# MCU_IMU.net
KiCad netlist of a schematic drawn in Altium Designer
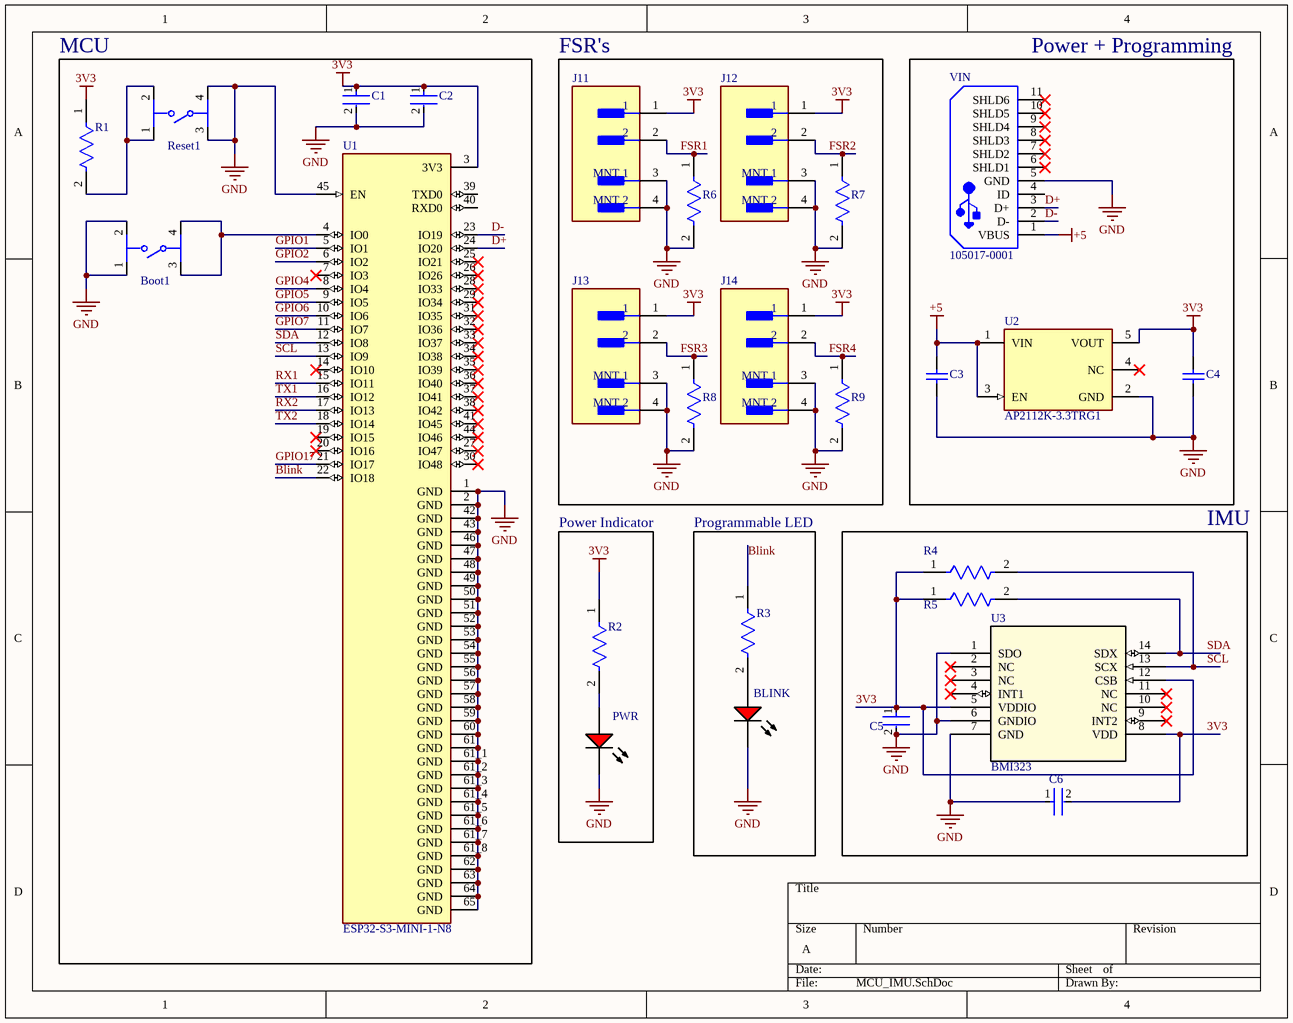
[diagram p0: MCU_IMU.SchDoc]

(export (version "E")
  (design (tool "Eeschema 10.0.6"))
  (components
    (comp (ref "BLINK")
      (value "SML-LX1206IC-TR")
      (footprint "LUMX-SML-LX1206IC_V")
      (description "LED Red, 65 mW, -40 to 85 degC, 2-Pin SMD, RoHS, Tape and Reel")
      (fields (field (name "MANUFACTURER") "Lumex"))
      (libsource (lib "Altium Content Vault") (part "LED-RED-AK-2"))
    )
    (comp (ref "Boot1")
      (value "PTS810SJM250SMTRLFS")
      (footprint "FP-PTS810SJM250SMTRLFS-MFG")
      (description "SWITCH TACTILE SPST-NO 0.05A 16V")
      (libsource (lib "Altium Content Vault") (part "1adf0dd01260c80cf25a44bfd6b99ba"))
    )
    (comp (ref "C1")
      (value "CC0805KRX7R9BB104")
      (footprint "FP-CC0805-0_85-MFG")
      (description "CAP CER 0.1UF 50V X7R 0805")
      (fields (field (name "TOLERANCE") "0.1") (field (name "MANUFACTURER") "Yageo"))
      (libsource (lib "Altium Content Vault") (part "11868f565c42a9108669ba33697ecf6"))
    )
    (comp (ref "C2")
      (value "CC0805KRX7R9BB104")
      (footprint "FP-CC0805-0_85-MFG")
      (description "CAP CER 0.1UF 50V X7R 0805")
      (fields (field (name "TOLERANCE") "0.1") (field (name "MANUFACTURER") "Yageo"))
      (libsource (lib "Altium Content Vault") (part "11868f565c42a9108669ba33697ecf6"))
    )
    (comp (ref "C3")
      (value "C0805C105K5RACTU")
      (footprint "CAPC2013X140X50ML20T25")
      (fields (field (name "MANUFACTURER") "Kemet"))
      (libsource (lib "Altium Content Vault") (part "CAP"))
    )
    (comp (ref "C4")
      (value "C0805C105K5RACTU")
      (footprint "CAPC2013X140X50ML20T25")
      (fields (field (name "MANUFACTURER") "Kemet"))
      (libsource (lib "Altium Content Vault") (part "CAP"))
    )
    (comp (ref "C5")
      (value "CC0805KRX7R9BB104")
      (footprint "FP-CC0805-0_85-MFG")
      (description "CAP CER 0.1UF 50V X7R 0805")
      (fields (field (name "TOLERANCE") "0.1") (field (name "MANUFACTURER") "Yageo"))
      (libsource (lib "Altium Content Vault") (part "11868f565c42a9108669ba33697ecf6"))
    )
    (comp (ref "C6")
      (value "CC0805KRX7R9BB104")
      (footprint "FP-CC0805-0_85-MFG")
      (description "CAP CER 0.1UF 50V X7R 0805")
      (fields (field (name "TOLERANCE") "0.1") (field (name "MANUFACTURER") "Yageo"))
      (libsource (lib "Altium Content Vault") (part "11868f565c42a9108669ba33697ecf6"))
    )
    (comp (ref "J11")
      (value "BM02B-SRSS-TBT(LF)(SN)")
      (footprint "FP-BM02B-SRSS-TBT_LF_SN-MFG")
      (description "CONN WIRE HDR 2POS 1MM STSMD")
      (libsource (lib "Altium Content Vault") (part "029478cb6d4f2fad0cd2a245525ee6d"))
    )
    (comp (ref "J12")
      (value "BM02B-SRSS-TBT(LF)(SN)")
      (footprint "FP-BM02B-SRSS-TBT_LF_SN-MFG")
      (description "CONN WIRE HDR 2POS 1MM STSMD")
      (libsource (lib "Altium Content Vault") (part "029478cb6d4f2fad0cd2a245525ee6d"))
    )
    (comp (ref "J13")
      (value "BM02B-SRSS-TBT(LF)(SN)")
      (footprint "FP-BM02B-SRSS-TBT_LF_SN-MFG")
      (description "CONN WIRE HDR 2POS 1MM STSMD")
      (libsource (lib "Altium Content Vault") (part "029478cb6d4f2fad0cd2a245525ee6d"))
    )
    (comp (ref "J14")
      (value "BM02B-SRSS-TBT(LF)(SN)")
      (footprint "FP-BM02B-SRSS-TBT_LF_SN-MFG")
      (description "CONN WIRE HDR 2POS 1MM STSMD")
      (libsource (lib "Altium Content Vault") (part "029478cb6d4f2fad0cd2a245525ee6d"))
    )
    (comp (ref "PWR")
      (value "SML-LX1206IC-TR")
      (footprint "LUMX-SML-LX1206IC_V")
      (description "LED Red, 65 mW, -40 to 85 degC, 2-Pin SMD, RoHS, Tape and Reel")
      (fields (field (name "MANUFACTURER") "Lumex"))
      (libsource (lib "Altium Content Vault") (part "LED-RED-AK-2"))
    )
    (comp (ref "R1")
      (value "CRCW08054K70FKEA")
      (footprint "FP-CRCW0805-e3-IPC_B")
      (description "RES Thick Film, 4.7kΩ, 1%, 0.125W, 100ppm/°C, 0805")
      (fields (field (name "TOLERANCE") "1%"))
      (libsource (lib "Altium Content Vault") (part "1029c3af85768c4190bb7ad29bc67b5"))
    )
    (comp (ref "R2")
      (value "CRCW08054K70FKEA")
      (footprint "FP-CRCW0805-e3-IPC_B")
      (description "RES Thick Film, 4.7kΩ, 1%, 0.125W, 100ppm/°C, 0805")
      (fields (field (name "TOLERANCE") "1%"))
      (libsource (lib "Altium Content Vault") (part "1029c3af85768c4190bb7ad29bc67b5"))
    )
    (comp (ref "R3")
      (value "CRCW08054K70FKEA")
      (footprint "FP-CRCW0805-e3-IPC_B")
      (description "RES Thick Film, 4.7kΩ, 1%, 0.125W, 100ppm/°C, 0805")
      (fields (field (name "TOLERANCE") "1%"))
      (libsource (lib "Altium Content Vault") (part "1029c3af85768c4190bb7ad29bc67b5"))
    )
    (comp (ref "R4")
      (value "CRCW08054K70FKEA")
      (footprint "FP-CRCW0805-e3-IPC_B")
      (description "RES Thick Film, 4.7kΩ, 1%, 0.125W, 100ppm/°C, 0805")
      (fields (field (name "TOLERANCE") "1%"))
      (libsource (lib "Altium Content Vault") (part "1029c3af85768c4190bb7ad29bc67b5"))
    )
    (comp (ref "R5")
      (value "CRCW08054K70FKEA")
      (footprint "FP-CRCW0805-e3-IPC_B")
      (description "RES Thick Film, 4.7kΩ, 1%, 0.125W, 100ppm/°C, 0805")
      (fields (field (name "TOLERANCE") "1%"))
      (libsource (lib "Altium Content Vault") (part "1029c3af85768c4190bb7ad29bc67b5"))
    )
    (comp (ref "R6")
      (value "RC0603FR-0710KL")
      (footprint "FP-RC0603-0_55-IPC_C")
      (description "RES 10K OHM 1% 1/10W 0603")
      (fields (field (name "TOLERANCE") "1%"))
      (libsource (lib "Altium Content Vault") (part "1029c3af85768c4190bb7ad29bc67b5"))
    )
    (comp (ref "R7")
      (value "RC0603FR-0710KL")
      (footprint "FP-RC0603-0_55-IPC_C")
      (description "RES 10K OHM 1% 1/10W 0603")
      (fields (field (name "TOLERANCE") "1%"))
      (libsource (lib "Altium Content Vault") (part "1029c3af85768c4190bb7ad29bc67b5"))
    )
    (comp (ref "R8")
      (value "RC0603FR-0710KL")
      (footprint "FP-RC0603-0_55-IPC_C")
      (description "RES 10K OHM 1% 1/10W 0603")
      (fields (field (name "TOLERANCE") "1%"))
      (libsource (lib "Altium Content Vault") (part "1029c3af85768c4190bb7ad29bc67b5"))
    )
    (comp (ref "R9")
      (value "RC0603FR-0710KL")
      (footprint "FP-RC0603-0_55-IPC_C")
      (description "RES 10K OHM 1% 1/10W 0603")
      (fields (field (name "TOLERANCE") "1%"))
      (libsource (lib "Altium Content Vault") (part "1029c3af85768c4190bb7ad29bc67b5"))
    )
    (comp (ref "Reset1")
      (value "PTS810SJM250SMTRLFS")
      (footprint "FP-PTS810SJM250SMTRLFS-MFG")
      (description "SWITCH TACTILE SPST-NO 0.05A 16V")
      (libsource (lib "Altium Content Vault") (part "1adf0dd01260c80cf25a44bfd6b99ba"))
    )
    (comp (ref "U1")
      (value "ESP32-S3-MINI-1-N8")
      (footprint "XCVR_ESP32-S3-MINI-1-N8")
      (fields (field (name "MF") "{'manufacturer': u'Espressif Systems'}"))
      (libsource (lib "Bryan Heddle") (part "ESP32-S3-MINI-1-N8"))
    )
    (comp (ref "U2")
      (value "AP2112K-3.3TRG1")
      (footprint "FP-SOT25-IPC_A")
      (description "IC REG LINEAR 3.3V 600MA SOT25")
      (libsource (lib "Altium Content Vault") (part "c8ab751aee5229183125ab046a11caa"))
    )
    (comp (ref "U3")
      (value "BMI323")
      (footprint "BMI323_BOS")
      (description "No Description Available")
      (fields (field (name "COPYRIGHT") "Copyright (C) 2025 Ultra Librarian. All rights reserved."))
      (libsource (lib "AI_Project_Library") (part "BMI323"))
    )
    (comp (ref "VIN")
      (value "105017-0001")
      (footprint "USB-MICRO-B_V")
      (fields (field (name "MANUFACTURER") "Molex"))
      (libsource (lib "Altium Content Vault") (part "USB-5-6SHLD"))
    )
  )
  (nets
    (net (code "1") (name "+5") (class "Default")
      (node (ref "C3") (pin "2") (pinfunction "2_2") (pintype "passive"))
      (node (ref "U2") (pin "1") (pinfunction "VIN_1") (pintype "power_in"))
      (node (ref "U2") (pin "3") (pinfunction "EN_3") (pintype "input"))
      (node (ref "VIN") (pin "1") (pinfunction "VBUS_1") (pintype "passive"))
    )
    (net (code "2") (name "/Blink") (class "Default")
      (node (ref "R3") (pin "1") (pinfunction "1_1") (pintype "passive"))
      (node (ref "U1") (pin "22") (pinfunction "IO18_22") (pintype "bidirectional"))
    )
    (net (code "3") (name "/D+") (class "Default")
      (node (ref "U1") (pin "24") (pinfunction "IO20_24") (pintype "bidirectional"))
      (node (ref "VIN") (pin "3") (pinfunction "D+_3") (pintype "passive"))
    )
    (net (code "4") (name "/D-") (class "Default")
      (node (ref "U1") (pin "23") (pinfunction "IO19_23") (pintype "bidirectional"))
      (node (ref "VIN") (pin "2") (pinfunction "D-_2") (pintype "passive"))
    )
    (net (code "5") (name "/FSR1") (class "Default")
      (node (ref "J11") (pin "2") (pinfunction "2_2") (pintype "passive"))
      (node (ref "R6") (pin "1") (pinfunction "1_1") (pintype "passive"))
    )
    (net (code "6") (name "/FSR2") (class "Default")
      (node (ref "J12") (pin "2") (pinfunction "2_2") (pintype "passive"))
      (node (ref "R7") (pin "1") (pinfunction "1_1") (pintype "passive"))
    )
    (net (code "7") (name "/FSR3") (class "Default")
      (node (ref "J13") (pin "2") (pinfunction "2_2") (pintype "passive"))
      (node (ref "R8") (pin "1") (pinfunction "1_1") (pintype "passive"))
    )
    (net (code "8") (name "/FSR4") (class "Default")
      (node (ref "J14") (pin "2") (pinfunction "2_2") (pintype "passive"))
      (node (ref "R9") (pin "1") (pinfunction "1_1") (pintype "passive"))
    )
    (net (code "9") (name "/GPIO1") (class "Default")
      (node (ref "U1") (pin "5") (pinfunction "IO1_5") (pintype "bidirectional"))
    )
    (net (code "10") (name "/GPIO2") (class "Default")
      (node (ref "U1") (pin "6") (pinfunction "IO2_6") (pintype "bidirectional"))
    )
    (net (code "11") (name "/GPIO4") (class "Default")
      (node (ref "U1") (pin "8") (pinfunction "IO4_8") (pintype "bidirectional"))
    )
    (net (code "12") (name "/GPIO5") (class "Default")
      (node (ref "U1") (pin "9") (pinfunction "IO5_9") (pintype "bidirectional"))
    )
    (net (code "13") (name "/GPIO6") (class "Default")
      (node (ref "U1") (pin "10") (pinfunction "IO6_10") (pintype "bidirectional"))
    )
    (net (code "14") (name "/GPIO7") (class "Default")
      (node (ref "U1") (pin "11") (pinfunction "IO7_11") (pintype "bidirectional"))
    )
    (net (code "15") (name "/GPIO17") (class "Default")
      (node (ref "U1") (pin "21") (pinfunction "IO17_21") (pintype "bidirectional"))
    )
    (net (code "16") (name "/RX1") (class "Default")
      (node (ref "U1") (pin "15") (pinfunction "IO11_15") (pintype "bidirectional"))
    )
    (net (code "17") (name "/RX2") (class "Default")
      (node (ref "U1") (pin "17") (pinfunction "IO13_17") (pintype "bidirectional"))
    )
    (net (code "18") (name "/SCL") (class "Default")
      (node (ref "R4") (pin "2") (pinfunction "2_2") (pintype "passive"))
      (node (ref "U1") (pin "13") (pinfunction "IO9_13") (pintype "bidirectional"))
      (node (ref "U3") (pin "13") (pinfunction "SCX_13") (pintype "input"))
    )
    (net (code "19") (name "/SDA") (class "Default")
      (node (ref "R5") (pin "2") (pinfunction "2_2") (pintype "passive"))
      (node (ref "U1") (pin "12") (pinfunction "IO8_12") (pintype "bidirectional"))
      (node (ref "U3") (pin "14") (pinfunction "SDX_14") (pintype "bidirectional"))
    )
    (net (code "20") (name "/TX1") (class "Default")
      (node (ref "U1") (pin "16") (pinfunction "IO12_16") (pintype "bidirectional"))
    )
    (net (code "21") (name "/TX2") (class "Default")
      (node (ref "U1") (pin "18") (pinfunction "IO14_18") (pintype "bidirectional"))
    )
    (net (code "22") (name "3V3") (class "Default")
      (node (ref "C1") (pin "1") (pinfunction "1_1") (pintype "passive"))
      (node (ref "C2") (pin "1") (pinfunction "1_1") (pintype "passive"))
      (node (ref "C4") (pin "2") (pinfunction "2_2") (pintype "passive"))
      (node (ref "C5") (pin "1") (pinfunction "1_1") (pintype "passive"))
      (node (ref "C6") (pin "2") (pinfunction "2_2") (pintype "passive"))
      (node (ref "J11") (pin "1") (pinfunction "1_1") (pintype "passive"))
      (node (ref "J12") (pin "1") (pinfunction "1_1") (pintype "passive"))
      (node (ref "J13") (pin "1") (pinfunction "1_1") (pintype "passive"))
      (node (ref "J14") (pin "1") (pinfunction "1_1") (pintype "passive"))
      (node (ref "R1") (pin "1") (pinfunction "1_1") (pintype "passive"))
      (node (ref "R2") (pin "1") (pinfunction "1_1") (pintype "passive"))
      (node (ref "R4") (pin "1") (pinfunction "1_1") (pintype "passive"))
      (node (ref "R5") (pin "1") (pinfunction "1_1") (pintype "passive"))
      (node (ref "U1") (pin "3") (pinfunction "3V3_3") (pintype "power_in"))
      (node (ref "U2") (pin "5") (pinfunction "VOUT_5") (pintype "power_in"))
      (node (ref "U3") (pin "12") (pinfunction "CSB_12") (pintype "input"))
      (node (ref "U3") (pin "5") (pinfunction "VDDIO_5") (pintype "power_in"))
      (node (ref "U3") (pin "8") (pinfunction "VDD_8") (pintype "power_in"))
    )
    (net (code "23") (name "GND") (class "Default")
      (node (ref "BLINK") (pin "2") (pinfunction "K_2") (pintype "passive"))
      (node (ref "Boot1") (pin "1") (pinfunction "1_1") (pintype "passive"))
      (node (ref "Boot1") (pin "2") (pinfunction "2_2") (pintype "passive"))
      (node (ref "C1") (pin "2") (pinfunction "2_2") (pintype "passive"))
      (node (ref "C2") (pin "2") (pinfunction "2_2") (pintype "passive"))
      (node (ref "C3") (pin "1") (pinfunction "1_1") (pintype "passive"))
      (node (ref "C4") (pin "1") (pinfunction "1_1") (pintype "passive"))
      (node (ref "C5") (pin "2") (pinfunction "2_2") (pintype "passive"))
      (node (ref "C6") (pin "1") (pinfunction "1_1") (pintype "passive"))
      (node (ref "J11") (pin "3") (pinfunction "MNT_1_3") (pintype "passive"))
      (node (ref "J11") (pin "4") (pinfunction "MNT_2_4") (pintype "passive"))
      (node (ref "J12") (pin "3") (pinfunction "MNT_1_3") (pintype "passive"))
      (node (ref "J12") (pin "4") (pinfunction "MNT_2_4") (pintype "passive"))
      (node (ref "J13") (pin "3") (pinfunction "MNT_1_3") (pintype "passive"))
      (node (ref "J13") (pin "4") (pinfunction "MNT_2_4") (pintype "passive"))
      (node (ref "J14") (pin "3") (pinfunction "MNT_1_3") (pintype "passive"))
      (node (ref "J14") (pin "4") (pinfunction "MNT_2_4") (pintype "passive"))
      (node (ref "PWR") (pin "2") (pinfunction "K_2") (pintype "passive"))
      (node (ref "R6") (pin "2") (pinfunction "2_2") (pintype "passive"))
      (node (ref "R7") (pin "2") (pinfunction "2_2") (pintype "passive"))
      (node (ref "R8") (pin "2") (pinfunction "2_2") (pintype "passive"))
      (node (ref "R9") (pin "2") (pinfunction "2_2") (pintype "passive"))
      (node (ref "Reset1") (pin "3") (pinfunction "3_3") (pintype "passive"))
      (node (ref "Reset1") (pin "4") (pinfunction "4_4") (pintype "passive"))
      (node (ref "U1") (pin "1") (pinfunction "GND_1") (pintype "power_in"))
      (node (ref "U1") (pin "2") (pinfunction "GND_2") (pintype "power_in"))
      (node (ref "U1") (pin "42") (pinfunction "GND_42") (pintype "power_in"))
      (node (ref "U1") (pin "43") (pinfunction "GND_43") (pintype "power_in"))
      (node (ref "U1") (pin "45") (pinfunction "EN_45") (pintype "input"))
      (node (ref "U1") (pin "46") (pinfunction "GND_46") (pintype "power_in"))
      (node (ref "U1") (pin "47") (pinfunction "GND_47") (pintype "power_in"))
      (node (ref "U1") (pin "48") (pinfunction "GND_48") (pintype "power_in"))
      (node (ref "U1") (pin "49") (pinfunction "GND_49") (pintype "power_in"))
      (node (ref "U1") (pin "50") (pinfunction "GND_50") (pintype "power_in"))
      (node (ref "U1") (pin "51") (pinfunction "GND_51") (pintype "power_in"))
      (node (ref "U1") (pin "52") (pinfunction "GND_52") (pintype "power_in"))
      (node (ref "U1") (pin "53") (pinfunction "GND_53") (pintype "power_in"))
      (node (ref "U1") (pin "54") (pinfunction "GND_54") (pintype "power_in"))
      (node (ref "U1") (pin "55") (pinfunction "GND_55") (pintype "power_in"))
      (node (ref "U1") (pin "56") (pinfunction "GND_56") (pintype "power_in"))
      (node (ref "U1") (pin "57") (pinfunction "GND_57") (pintype "power_in"))
      (node (ref "U1") (pin "58") (pinfunction "GND_58") (pintype "power_in"))
      (node (ref "U1") (pin "59") (pinfunction "GND_59") (pintype "power_in"))
      (node (ref "U1") (pin "60") (pinfunction "GND_60") (pintype "power_in"))
      (node (ref "U1") (pin "61") (pinfunction "GND_61") (pintype "power_in"))
      (node (ref "U1") (pin "61_1") (pinfunction "GND_61_1") (pintype "power_in"))
      (node (ref "U1") (pin "61_2") (pinfunction "GND_61_2") (pintype "power_in"))
      (node (ref "U1") (pin "61_3") (pinfunction "GND_61_3") (pintype "power_in"))
      (node (ref "U1") (pin "61_4") (pinfunction "GND_61_4") (pintype "power_in"))
      (node (ref "U1") (pin "61_5") (pinfunction "GND_61_5") (pintype "power_in"))
      (node (ref "U1") (pin "61_6") (pinfunction "GND_61_6") (pintype "power_in"))
      (node (ref "U1") (pin "61_7") (pinfunction "GND_61_7") (pintype "power_in"))
      (node (ref "U1") (pin "61_8") (pinfunction "GND_61_8") (pintype "power_in"))
      (node (ref "U1") (pin "62") (pinfunction "GND_62") (pintype "power_in"))
      (node (ref "U1") (pin "63") (pinfunction "GND_63") (pintype "power_in"))
      (node (ref "U1") (pin "64") (pinfunction "GND_64") (pintype "power_in"))
      (node (ref "U1") (pin "65") (pinfunction "GND_65") (pintype "power_in"))
      (node (ref "U2") (pin "2") (pinfunction "GND_2") (pintype "power_in"))
      (node (ref "U3") (pin "1") (pinfunction "SDO_1") (pintype "passive"))
      (node (ref "U3") (pin "6") (pinfunction "GNDIO_6") (pintype "power_in"))
      (node (ref "U3") (pin "7") (pinfunction "GND_7") (pintype "power_in"))
      (node (ref "VIN") (pin "5") (pinfunction "GND_5") (pintype "passive"))
    )
    (net (code "24") (name "Net-(BLINK-A)") (class "Default")
      (node (ref "BLINK") (pin "1") (pinfunction "A_1") (pintype "passive"))
      (node (ref "R3") (pin "2") (pinfunction "2_2") (pintype "passive"))
    )
    (net (code "25") (name "Net-(PWR-A)") (class "Default")
      (node (ref "PWR") (pin "1") (pinfunction "A_1") (pintype "passive"))
      (node (ref "R2") (pin "2") (pinfunction "2_2") (pintype "passive"))
    )
    (net (code "26") (name "Net-(R1-Pad2)") (class "Default")
      (node (ref "R1") (pin "2") (pinfunction "2_2") (pintype "passive"))
      (node (ref "Reset1") (pin "1") (pinfunction "1_1") (pintype "passive"))
      (node (ref "Reset1") (pin "2") (pinfunction "2_2") (pintype "passive"))
    )
    (net (code "27") (name "Net-(U1-IO0)") (class "Default")
      (node (ref "Boot1") (pin "3") (pinfunction "3_3") (pintype "passive"))
      (node (ref "Boot1") (pin "4") (pinfunction "4_4") (pintype "passive"))
      (node (ref "U1") (pin "4") (pinfunction "IO0_4") (pintype "bidirectional"))
    )
    (net (code "28") (name "unconnected-(U1-IO3-Pad7)") (class "Default")
      (node (ref "U1") (pin "7") (pinfunction "IO3_7") (pintype "bidirectional+no_connect"))
    )
    (net (code "29") (name "unconnected-(U1-IO10-Pad14)") (class "Default")
      (node (ref "U1") (pin "14") (pinfunction "IO10_14") (pintype "bidirectional+no_connect"))
    )
    (net (code "30") (name "unconnected-(U1-IO15-Pad19)") (class "Default")
      (node (ref "U1") (pin "19") (pinfunction "IO15_19") (pintype "bidirectional+no_connect"))
    )
    (net (code "31") (name "unconnected-(U1-IO16-Pad20)") (class "Default")
      (node (ref "U1") (pin "20") (pinfunction "IO16_20") (pintype "bidirectional+no_connect"))
    )
    (net (code "32") (name "unconnected-(U1-IO21-Pad25)") (class "Default")
      (node (ref "U1") (pin "25") (pinfunction "IO21_25") (pintype "bidirectional+no_connect"))
    )
    (net (code "33") (name "unconnected-(U1-IO26-Pad26)") (class "Default")
      (node (ref "U1") (pin "26") (pinfunction "IO26_26") (pintype "bidirectional+no_connect"))
    )
    (net (code "34") (name "unconnected-(U1-IO33-Pad28)") (class "Default")
      (node (ref "U1") (pin "28") (pinfunction "IO33_28") (pintype "bidirectional+no_connect"))
    )
    (net (code "35") (name "unconnected-(U1-IO34-Pad29)") (class "Default")
      (node (ref "U1") (pin "29") (pinfunction "IO34_29") (pintype "bidirectional+no_connect"))
    )
    (net (code "36") (name "unconnected-(U1-IO35-Pad31)") (class "Default")
      (node (ref "U1") (pin "31") (pinfunction "IO35_31") (pintype "bidirectional+no_connect"))
    )
    (net (code "37") (name "unconnected-(U1-IO36-Pad32)") (class "Default")
      (node (ref "U1") (pin "32") (pinfunction "IO36_32") (pintype "bidirectional+no_connect"))
    )
    (net (code "38") (name "unconnected-(U1-IO37-Pad33)") (class "Default")
      (node (ref "U1") (pin "33") (pinfunction "IO37_33") (pintype "bidirectional+no_connect"))
    )
    (net (code "39") (name "unconnected-(U1-IO38-Pad34)") (class "Default")
      (node (ref "U1") (pin "34") (pinfunction "IO38_34") (pintype "bidirectional+no_connect"))
    )
    (net (code "40") (name "unconnected-(U1-IO39-Pad35)") (class "Default")
      (node (ref "U1") (pin "35") (pinfunction "IO39_35") (pintype "bidirectional+no_connect"))
    )
    (net (code "41") (name "unconnected-(U1-IO40-Pad36)") (class "Default")
      (node (ref "U1") (pin "36") (pinfunction "IO40_36") (pintype "bidirectional+no_connect"))
    )
    (net (code "42") (name "unconnected-(U1-IO41-Pad37)") (class "Default")
      (node (ref "U1") (pin "37") (pinfunction "IO41_37") (pintype "bidirectional+no_connect"))
    )
    (net (code "43") (name "unconnected-(U1-IO42-Pad38)") (class "Default")
      (node (ref "U1") (pin "38") (pinfunction "IO42_38") (pintype "bidirectional+no_connect"))
    )
    (net (code "44") (name "unconnected-(U1-IO45-Pad41)") (class "Default")
      (node (ref "U1") (pin "41") (pinfunction "IO45_41") (pintype "bidirectional+no_connect"))
    )
    (net (code "45") (name "unconnected-(U1-IO46-Pad44)") (class "Default")
      (node (ref "U1") (pin "44") (pinfunction "IO46_44") (pintype "bidirectional+no_connect"))
    )
    (net (code "46") (name "unconnected-(U1-IO47-Pad27)") (class "Default")
      (node (ref "U1") (pin "27") (pinfunction "IO47_27") (pintype "bidirectional+no_connect"))
    )
    (net (code "47") (name "unconnected-(U1-IO48-Pad30)") (class "Default")
      (node (ref "U1") (pin "30") (pinfunction "IO48_30") (pintype "bidirectional+no_connect"))
    )
    (net (code "48") (name "unconnected-(U1-RXD0-Pad40)") (class "Default")
      (node (ref "U1") (pin "40") (pinfunction "RXD0_40") (pintype "bidirectional"))
    )
    (net (code "49") (name "unconnected-(U1-TXD0-Pad39)") (class "Default")
      (node (ref "U1") (pin "39") (pinfunction "TXD0_39") (pintype "bidirectional"))
    )
    (net (code "50") (name "unconnected-(U2-NC-Pad4)") (class "Default")
      (node (ref "U2") (pin "4") (pinfunction "NC_4") (pintype "passive+no_connect"))
    )
    (net (code "51") (name "unconnected-(U3-INT1-Pad4)") (class "Default")
      (node (ref "U3") (pin "4") (pinfunction "INT1_4") (pintype "bidirectional+no_connect"))
    )
    (net (code "52") (name "unconnected-(U3-INT2-Pad9)") (class "Default")
      (node (ref "U3") (pin "9") (pinfunction "INT2_9") (pintype "bidirectional+no_connect"))
    )
    (net (code "53") (name "unconnected-(U3-NC-Pad2)") (class "Default")
      (node (ref "U3") (pin "2") (pinfunction "NC_2") (pintype "passive+no_connect"))
    )
    (net (code "54") (name "unconnected-(U3-NC-Pad3)") (class "Default")
      (node (ref "U3") (pin "3") (pinfunction "NC_3") (pintype "passive+no_connect"))
    )
    (net (code "55") (name "unconnected-(U3-NC-Pad10)") (class "Default")
      (node (ref "U3") (pin "10") (pinfunction "NC_10") (pintype "passive+no_connect"))
    )
    (net (code "56") (name "unconnected-(U3-NC-Pad11)") (class "Default")
      (node (ref "U3") (pin "11") (pinfunction "NC_11") (pintype "passive+no_connect"))
    )
    (net (code "57") (name "unconnected-(VIN-ID-Pad4)") (class "Default")
      (node (ref "VIN") (pin "4") (pinfunction "ID_4") (pintype "passive"))
    )
    (net (code "58") (name "unconnected-(VIN-SHLD1-Pad6)") (class "Default")
      (node (ref "VIN") (pin "6") (pinfunction "SHLD1_6") (pintype "passive+no_connect"))
    )
    (net (code "59") (name "unconnected-(VIN-SHLD2-Pad7)") (class "Default")
      (node (ref "VIN") (pin "7") (pinfunction "SHLD2_7") (pintype "passive+no_connect"))
    )
    (net (code "60") (name "unconnected-(VIN-SHLD3-Pad8)") (class "Default")
      (node (ref "VIN") (pin "8") (pinfunction "SHLD3_8") (pintype "passive+no_connect"))
    )
    (net (code "61") (name "unconnected-(VIN-SHLD4-Pad9)") (class "Default")
      (node (ref "VIN") (pin "9") (pinfunction "SHLD4_9") (pintype "passive+no_connect"))
    )
    (net (code "62") (name "unconnected-(VIN-SHLD5-Pad10)") (class "Default")
      (node (ref "VIN") (pin "10") (pinfunction "SHLD5_10") (pintype "passive+no_connect"))
    )
    (net (code "63") (name "unconnected-(VIN-SHLD6-Pad11)") (class "Default")
      (node (ref "VIN") (pin "11") (pinfunction "SHLD6_11") (pintype "passive+no_connect"))
    )
  )
)
